# v001.net
KiCad netlist of a schematic drawn in EAGLE
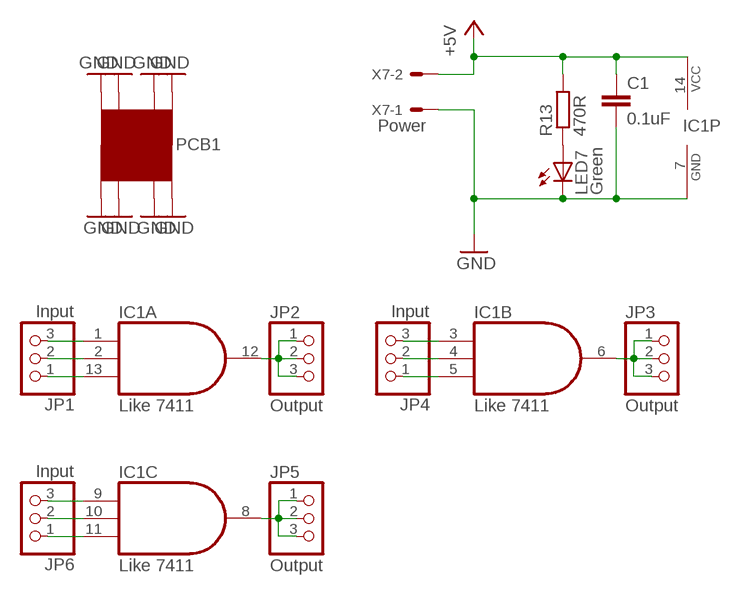
[diagram p0: schematic, sheet 1]

(export (version "E")
  (design (tool "Eeschema 10.0.6"))
  (components
    (comp (ref "C1")
      (value "0.1uF")
      (footprint "eagle-import:C050-024X044")
      (libsource (lib "eagle-import") (part "C-EU050-024X044"))
    )
    (comp (ref "IC1")
      (value "Like 7411")
      (footprint "eagle-import:DIL14")
      (libsource (lib "eagle-import") (part "7411NALS"))
    )
    (comp (ref "JP1")
      (value "Input")
      (footprint "eagle-import:1X03")
      (libsource (lib "eagle-import") (part "PINHD-1X3"))
    )
    (comp (ref "JP2")
      (value "Output")
      (footprint "eagle-import:1X03")
      (libsource (lib "eagle-import") (part "PINHD-1X3"))
    )
    (comp (ref "JP3")
      (value "Output")
      (footprint "eagle-import:1X03")
      (libsource (lib "eagle-import") (part "PINHD-1X3"))
    )
    (comp (ref "JP4")
      (value "Input")
      (footprint "eagle-import:1X03")
      (libsource (lib "eagle-import") (part "PINHD-1X3"))
    )
    (comp (ref "JP5")
      (value "Output")
      (footprint "eagle-import:1X03")
      (libsource (lib "eagle-import") (part "PINHD-1X3"))
    )
    (comp (ref "JP6")
      (value "Input")
      (footprint "eagle-import:1X03")
      (libsource (lib "eagle-import") (part "PINHD-1X3"))
    )
    (comp (ref "LED7")
      (value "Green")
      (footprint "eagle-import:LED3MM")
      (libsource (lib "eagle-import") (part "LED3MM"))
    )
    (comp (ref "PCB1")
      (value "PCB05X05")
      (footprint "eagle-import:PCB_05X05")
      (libsource (lib "eagle-import") (part "PCB05X05"))
    )
    (comp (ref "R13")
      (value "470R")
      (footprint "eagle-import:0204_7")
      (libsource (lib "eagle-import") (part "R-EU_0204/7"))
    )
    (comp (ref "X7")
      (value "Power")
      (footprint "eagle-import:6410-02")
      (libsource (lib "eagle-import") (part "22-?-0227-2021"))
    )
  )
  (nets
    (net (code "1") (name "+5V") (class "Default")
      (node (ref "C1") (pin "1") (pinfunction "1_1") (pintype "passive"))
      (node (ref "IC1") (pin "14") (pinfunction "VCC_14") (pintype "power_in"))
      (node (ref "R13") (pin "2") (pinfunction "2_2") (pintype "passive"))
      (node (ref "X7") (pin "2") (pinfunction "S_2") (pintype "passive"))
    )
    (net (code "2") (name "GND") (class "Default")
      (node (ref "C1") (pin "2") (pinfunction "2_2") (pintype "passive"))
      (node (ref "IC1") (pin "7") (pinfunction "GND_7") (pintype "power_in"))
      (node (ref "LED7") (pin "K") (pinfunction "C_K") (pintype "passive"))
      (node (ref "PCB1") (pin "GND@1") (pinfunction "GND_GND@1") (pintype "bidirectional"))
      (node (ref "PCB1") (pin "GND@2") (pinfunction "GND_GND@2") (pintype "bidirectional"))
      (node (ref "PCB1") (pin "GND@3") (pinfunction "GND_GND@3") (pintype "bidirectional"))
      (node (ref "PCB1") (pin "GND@4") (pinfunction "GND_GND@4") (pintype "bidirectional"))
      (node (ref "PCB1") (pin "GND@5") (pinfunction "GND_GND@5") (pintype "bidirectional"))
      (node (ref "PCB1") (pin "GND@6") (pinfunction "GND_GND@6") (pintype "bidirectional"))
      (node (ref "PCB1") (pin "GND@7") (pinfunction "GND_GND@7") (pintype "bidirectional"))
      (node (ref "PCB1") (pin "GND@8") (pinfunction "GND_GND@8") (pintype "bidirectional"))
      (node (ref "X7") (pin "1") (pinfunction "S_1") (pintype "passive"))
    )
    (net (code "3") (name "Net-(IC1A-I0)") (class "Default")
      (node (ref "IC1") (pin "1") (pinfunction "I0_1") (pintype "input"))
      (node (ref "JP1") (pin "3") (pinfunction "3_3") (pintype "passive"))
    )
    (net (code "4") (name "Net-(IC1A-I1)") (class "Default")
      (node (ref "IC1") (pin "2") (pinfunction "I1_2") (pintype "input"))
      (node (ref "JP1") (pin "2") (pinfunction "2_2") (pintype "passive"))
    )
    (net (code "5") (name "Net-(IC1A-I2)") (class "Default")
      (node (ref "IC1") (pin "13") (pinfunction "I2_13") (pintype "input"))
      (node (ref "JP1") (pin "1") (pinfunction "1_1") (pintype "passive"))
    )
    (net (code "6") (name "Net-(IC1A-O)") (class "Default")
      (node (ref "IC1") (pin "12") (pinfunction "O_12") (pintype "output"))
      (node (ref "JP2") (pin "1") (pinfunction "1_1") (pintype "passive"))
      (node (ref "JP2") (pin "2") (pinfunction "2_2") (pintype "passive"))
      (node (ref "JP2") (pin "3") (pinfunction "3_3") (pintype "passive"))
    )
    (net (code "7") (name "Net-(IC1B-I0)") (class "Default")
      (node (ref "IC1") (pin "3") (pinfunction "I0_3") (pintype "input"))
      (node (ref "JP4") (pin "3") (pinfunction "3_3") (pintype "passive"))
    )
    (net (code "8") (name "Net-(IC1B-I1)") (class "Default")
      (node (ref "IC1") (pin "4") (pinfunction "I1_4") (pintype "input"))
      (node (ref "JP4") (pin "2") (pinfunction "2_2") (pintype "passive"))
    )
    (net (code "9") (name "Net-(IC1B-I2)") (class "Default")
      (node (ref "IC1") (pin "5") (pinfunction "I2_5") (pintype "input"))
      (node (ref "JP4") (pin "1") (pinfunction "1_1") (pintype "passive"))
    )
    (net (code "10") (name "Net-(IC1B-O)") (class "Default")
      (node (ref "IC1") (pin "6") (pinfunction "O_6") (pintype "output"))
      (node (ref "JP3") (pin "1") (pinfunction "1_1") (pintype "passive"))
      (node (ref "JP3") (pin "2") (pinfunction "2_2") (pintype "passive"))
      (node (ref "JP3") (pin "3") (pinfunction "3_3") (pintype "passive"))
    )
    (net (code "11") (name "Net-(IC1C-I0)") (class "Default")
      (node (ref "IC1") (pin "9") (pinfunction "I0_9") (pintype "input"))
      (node (ref "JP6") (pin "3") (pinfunction "3_3") (pintype "passive"))
    )
    (net (code "12") (name "Net-(IC1C-I1)") (class "Default")
      (node (ref "IC1") (pin "10") (pinfunction "I1_10") (pintype "input"))
      (node (ref "JP6") (pin "2") (pinfunction "2_2") (pintype "passive"))
    )
    (net (code "13") (name "Net-(IC1C-I2)") (class "Default")
      (node (ref "IC1") (pin "11") (pinfunction "I2_11") (pintype "input"))
      (node (ref "JP6") (pin "1") (pinfunction "1_1") (pintype "passive"))
    )
    (net (code "14") (name "Net-(IC1C-O)") (class "Default")
      (node (ref "IC1") (pin "8") (pinfunction "O_8") (pintype "output"))
      (node (ref "JP5") (pin "1") (pinfunction "1_1") (pintype "passive"))
      (node (ref "JP5") (pin "2") (pinfunction "2_2") (pintype "passive"))
      (node (ref "JP5") (pin "3") (pinfunction "3_3") (pintype "passive"))
    )
    (net (code "15") (name "Net-(LED7-PadA)") (class "Default")
      (node (ref "LED7") (pin "A") (pinfunction "A_A") (pintype "passive"))
      (node (ref "R13") (pin "1") (pinfunction "1_1") (pintype "passive"))
    )
  )
)
